# 8__MOT_CONNECTOR.net
KiCad netlist of a schematic drawn in Altium Designer
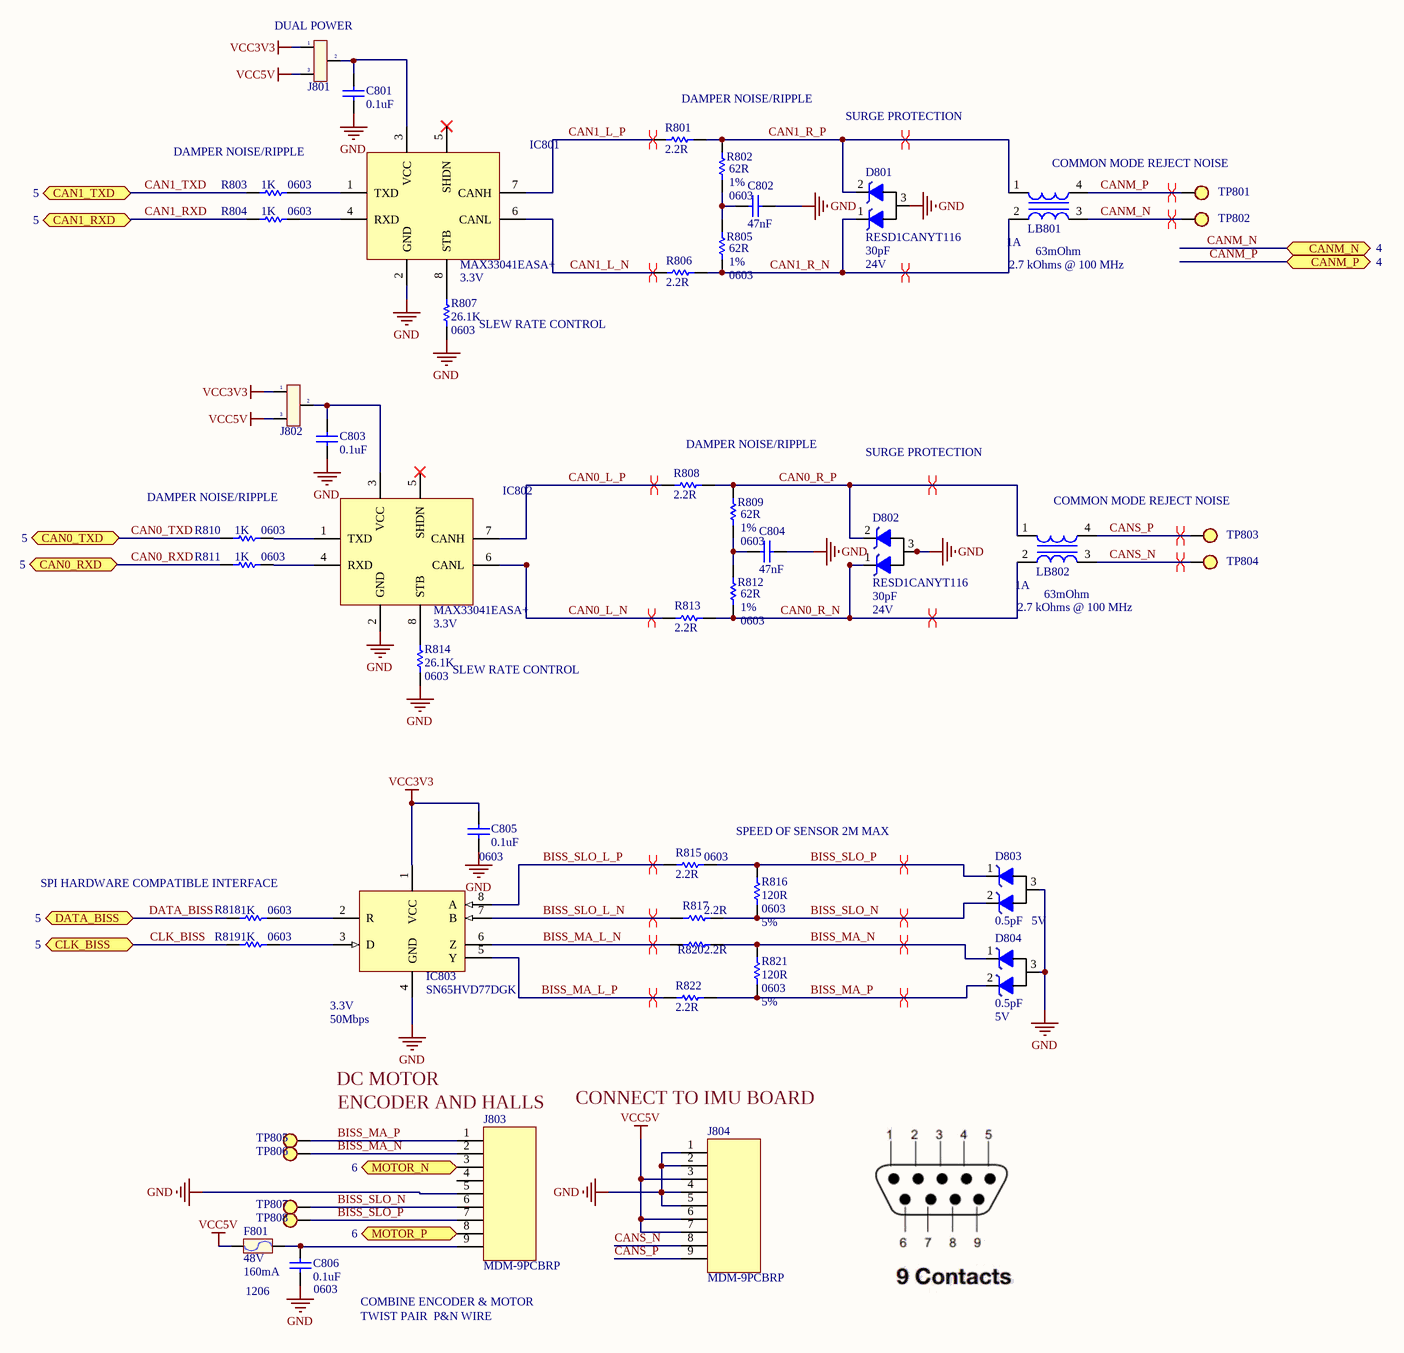
[diagram p0: [8]_MOT_CONNECTOR.SchDoc]

(export (version "E")
  (design (tool "Eeschema 10.0.6"))
  (components
    (comp (ref "C801")
      (value "0.1uF")
      (footprint "CAP 0603")
      (description "CAP-CER,SMD;0.1UF,10%,50V,X7R,0603")
      (fields (field (name "VOLTAGE") "50V") (field (name "TOLERANCE") "±10%"))
      (libsource (lib "Slider") (part "Cap"))
    )
    (comp (ref "C802")
      (value "47nF")
      (footprint "CAP 0603")
      (description "CAP-CER,SMD; 47nF,10%,50V,X7R,0603")
      (fields (field (name "VOLTAGE") "50V") (field (name "TOLERANCE") "±10%"))
      (libsource (lib "Slider") (part "Cap"))
    )
    (comp (ref "C803")
      (value "0.1uF")
      (footprint "CAP 0603")
      (description "CAP-CER,SMD;0.1UF,10%,50V,X7R,0603")
      (fields (field (name "VOLTAGE") "50V") (field (name "TOLERANCE") "±10%"))
      (libsource (lib "Slider") (part "Cap"))
    )
    (comp (ref "C804")
      (value "47nF")
      (footprint "CAP 0603")
      (description "CAP-CER,SMD; 47nF,10%,50V,X7R,0603")
      (fields (field (name "VOLTAGE") "50V") (field (name "TOLERANCE") "±10%"))
      (libsource (lib "Slider") (part "Cap"))
    )
    (comp (ref "C805")
      (value "0.1uF")
      (footprint "0603")
      (description "CAP-CER,SMD;0.1UF,10%,50V,X7R,0603")
      (fields (field (name "VOLTAGE") "50V") (field (name "TOLERANCE") "±10%"))
      (libsource (lib "Slider") (part "Cap"))
    )
    (comp (ref "C806")
      (value "0.1uF")
      (footprint "0603")
      (description "CAP-CER,SMD;0.1UF,10%,50V,X7R,0603")
      (fields (field (name "VOLTAGE") "50V") (field (name "TOLERANCE") "±10%"))
      (libsource (lib "Slider") (part "Cap"))
    )
    (comp (ref "D801")
      (value "RESD1CANYT116")
      (footprint "SOT-23-3")
      (description "TVS DIODE 24VWM 50VC SOT23-")
      (fields
        (field (name "POWER") "230W")
        (field (name "CAPACITANCE") "30pF")
        (field (name "VOLTAGE") "24V")
      )
      (libsource (lib "My Library") (part "TVS_DUAL_SIGNAL_5V_SOT23"))
    )
    (comp (ref "D802")
      (value "RESD1CANYT116")
      (footprint "SOT-23-3")
      (description "TVS DIODE 24VWM 50VC SOT23-")
      (fields
        (field (name "POWER") "230W")
        (field (name "CAPACITANCE") "30pF")
        (field (name "VOLTAGE") "24V")
      )
      (libsource (lib "My Library") (part "TVS_DUAL_SIGNAL_5V_SOT23"))
    )
    (comp (ref "D803")
      (value "ESDR0502BT1G")
      (footprint "SOT-416")
      (description "5V, ESD PROTECTION DEVICES, SOT-23")
      (fields
        (field (name "MANUFACTURER2_PART#") "DF3D6.8MS,LF")
        (field (name "POWER") "320W")
        (field (name "CAPACITANCE") "0.5pF")
        (field (name "VOLTAGE") "5V")
      )
      (libsource (lib "") (part "TVS_DUAL_SIGNAL_5V_SOT23_1"))
    )
    (comp (ref "D804")
      (value "ESDR0502BT1G")
      (footprint "SOT-416")
      (description "5V, ESD PROTECTION DEVICES, SOT-23")
      (fields
        (field (name "MANUFACTURER2_PART#") "DF3D6.8MS,LF")
        (field (name "POWER") "320W")
        (field (name "CAPACITANCE") "0.5pF")
        (field (name "VOLTAGE") "5V")
      )
      (libsource (lib "") (part "TVS_DUAL_SIGNAL_5V_SOT23_1"))
    )
    (comp (ref "F801")
      (value "0ZCG0014FF2C")
      (footprint "RES 1206")
      (description "PTC RESET FUSE 48V 160MA 1206")
      (fields
        (field (name "MANUFACTURER1_PART#") "0ZCJ0016FF2E")
        (field (name "MANUFACTURER2_PART#") "CLA1684")
        (field (name "VOLTAGE - RATED") "48V")
        (field (name "PACKAGE / CASE") "1206")
        (field (name "CURRENT RATING (AMPS)") "160mA")
      )
      (libsource (lib "K Shematic") (part "0875.800MXEP"))
    )
    (comp (ref "IC801")
      (value "MAX33041EASA+")
      (footprint "8-SOIC")
      (description "IC CAN TXRX 3.3V 2MBPS SOIC")
      (fields (field (name "MANUFACTURER PART NUMBER") "MAX33041EASA+") (field (name "VOLTAGE") "3.3V"))
      (libsource (lib "OE Seeker-IsolatedPower") (part "IC;IC CAN TRANSEIVER HS,8SOIC,-40TO150°C,TJA1042T/3,118"))
    )
    (comp (ref "IC802")
      (value "MAX33041EASA+")
      (footprint "8-SOIC")
      (description "IC CAN TXRX 3.3V 2MBPS SOIC")
      (fields (field (name "MANUFACTURER PART NUMBER") "MAX33041EASA+") (field (name "VOLTAGE") "3.3V"))
      (libsource (lib "OE Seeker-IsolatedPower") (part "IC;IC CAN TRANSEIVER HS,8SOIC,-40TO150°C,TJA1042T/3,118"))
    )
    (comp (ref "IC803")
      (value "IC;IC TRANSCEIVER FULL 1/1 8SOIC,8-SOIC,-40TO 85°C,SN65HVD77DR")
      (footprint "8-VSSOP")
      (description "IC TRANSCEIVER FULL 1/1 8VSSOP")
      (fields
        (field (name "MANUFACTURER") "TI")
        (field (name "MANUFACTURER PART NUMBER") "SN65HVD77DGK")
        (field (name "MANUFACTURER1_PART#") "SN65HVD77DGK")
        (field (name "VOLTAGE") "3.3V")
        (field (name "SPEED") "50Mbps")
      )
      (libsource (lib "DRIVER MOTION TILT_NEW") (part "IC;IC TRANSCEIVER FULL 1/1 8SOIC,8-SOIC,-40TO 85°C,SN65HVD77DR"))
    )
    (comp (ref "J801")
      (value "JP 2-1")
      (footprint "JP3")
      (description "Jumper 2-1")
      (libsource (lib "ThanhSchematicLib") (part "JP 2-1"))
    )
    (comp (ref "J802")
      (value "JP 2-1")
      (footprint "JP3")
      (description "Jumper 2-1")
      (libsource (lib "ThanhSchematicLib") (part "JP 2-1"))
    )
    (comp (ref "J803")
      (value "CONN-DIP;CONN MICRO-D PLUG 9POS R/A SLDR,M,MDM-9PCBRP")
      (footprint "MDM-9PCBRP")
      (description "CONN MICRO-D PLUG 9POS R/A SLDR")
      (fields
        (field (name "MANUFACTURER") "ITT CANNON, LLC")
        (field (name "MANUFACTURER PART NUMBER") "MDM-9PCBRP")
        (field (name "MANUFACTURER1_PART#") "MDM-9PCBRP")
      )
      (libsource (lib "DRIVER MOTION PAN_NEW") (part "CONN-DIP;CONN MICRO-D PLUG 9POS R/A SLDR,M,MDM-9PCBRP"))
    )
    (comp (ref "J804")
      (value "CONN-DIP;CONN MICRO-D PLUG 9POS R/A SLDR,M,MDM-9PCBRP")
      (footprint "MDM-9PCBRP")
      (description "CONN MICRO-D PLUG 9POS R/A SLDR")
      (fields
        (field (name "MANUFACTURER") "ITT CANNON, LLC")
        (field (name "MANUFACTURER PART NUMBER") "MDM-9PCBRP")
        (field (name "MANUFACTURER1_PART#") "MDM-9PCBRP")
      )
      (libsource (lib "IMU_NEW") (part "CONN-DIP;CONN MICRO-D PLUG 9POS R/A SLDR,M,MDM-9PCBRP"))
    )
    (comp (ref "LB801")
      (value "MCM-7060M-272-RU")
      (footprint "MCM-7060M")
      (description "CMC 1A 2LN 2.7KOHM SMD")
      (fields
        (field (name "CURRENT") "1A")
        (field (name "IMPEDANCE") "2.7 kOhms @ 100 MHz")
        (field (name "DCR") "63mOhm")
      )
      (libsource (lib "OE Seeker-IsolatedPower") (part "CHOKE-SMD;90OHM@100MHz,0.15A,5V,DLP11SA900HL2L"))
    )
    (comp (ref "LB802")
      (value "MCM-7060M-272-RU")
      (footprint "MCM-7060M")
      (description "CMC 1A 2LN 2.7KOHM SMD")
      (fields
        (field (name "CURRENT") "1A")
        (field (name "IMPEDANCE") "2.7 kOhms @ 100 MHz")
        (field (name "DCR") "63mOhm")
      )
      (libsource (lib "OE Seeker-IsolatedPower") (part "CHOKE-SMD;90OHM@100MHz,0.15A,5V,DLP11SA900HL2L"))
    )
    (comp (ref "R801")
      (value "2.2R")
      (footprint "res 0603")
      (description "RES SMD 2.2 OHM 5% 1/10W 0603")
      (fields
        (field (name "MANUFACTURER1_PART#") "RC0603JR-072R2L")
        (field (name "MANUFACTURER2_PART#") "RMCF0603JT2R20")
      )
      (libsource (lib "Full") (part "Res0.3"))
    )
    (comp (ref "R802")
      (value "62R")
      (footprint "R0603")
      (description "RES SM 62 OHM 1% 1/10W 0603")
      (fields
        (field (name "MANUFACTURER1_PART#") "RMCF0603FT62R0")
        (field (name "MANUFACTURER2_PART#") "RC0603FR-0762RL")
        (field (name "TOLERANCE") "1%")
        (field (name "PACKAGE") "0603")
      )
      (libsource (lib "OE Seeker-IsolatedPower") (part "RES-SMD;60.4OHM,1%,0402,1/10W"))
    )
    (comp (ref "R803")
      (value "1K")
      (footprint "res 0603")
      (description "RES SMD,1K OHM,5%,1/10W,0603")
      (fields
        (field (name "MANUFACTURER1_PART#") "RMCF06031K00JNEAC")
        (field (name "MANUFACTURER2_PART#") "R0603J1KTG")
        (field (name "PCB FOOTPRINT") "0603")
      )
      (libsource (lib "Full") (part "Res0.3"))
    )
    (comp (ref "R804")
      (value "1K")
      (footprint "res 0603")
      (description "RES SMD,1K OHM,5%,1/10W,0603")
      (fields
        (field (name "MANUFACTURER1_PART#") "RMCF06031K00JNEAC")
        (field (name "MANUFACTURER2_PART#") "R0603J1KTG")
        (field (name "PCB FOOTPRINT") "0603")
      )
      (libsource (lib "Full") (part "Res0.3"))
    )
    (comp (ref "R805")
      (value "62R")
      (footprint "R0603")
      (description "RES SM 62 OHM 1% 1/10W 0603")
      (fields
        (field (name "MANUFACTURER1_PART#") "RMCF0603FT62R0")
        (field (name "MANUFACTURER2_PART#") "RC0603FR-0762RL")
        (field (name "TOLERANCE") "1%")
        (field (name "PACKAGE") "0603")
      )
      (libsource (lib "OE Seeker-IsolatedPower") (part "RES-SMD;60.4OHM,1%,0402,1/10W"))
    )
    (comp (ref "R806")
      (value "2.2R")
      (footprint "res 0603")
      (description "RES SMD 2.2 OHM 5% 1/10W 0603")
      (fields
        (field (name "MANUFACTURER1_PART#") "RC0603JR-072R2L")
        (field (name "MANUFACTURER2_PART#") "RMCF0603JT2R20")
      )
      (libsource (lib "Full") (part "Res0.3"))
    )
    (comp (ref "R807")
      (value "26.1K")
      (footprint "R0603")
      (description "RES 26.1K OHM 1% 1/10W 0603")
      (fields
        (field (name "MANUFACTURER1_PART#") "RMCF0603FT26K1")
        (field (name "MANUFACTURER2_PART#") "RC0603FR-0726K1L")
        (field (name "PCB FOOTPRINT") "0603")
      )
      (libsource (lib "altium-import") (part "root_3_Res0.3_"))
    )
    (comp (ref "R808")
      (value "2.2R")
      (footprint "res 0603")
      (description "RES SMD 2.2 OHM 5% 1/10W 0603")
      (fields
        (field (name "MANUFACTURER1_PART#") "RC0603JR-072R2L")
        (field (name "MANUFACTURER2_PART#") "RMCF0603JT2R20")
      )
      (libsource (lib "Full") (part "Res0.3"))
    )
    (comp (ref "R809")
      (value "62R")
      (footprint "R0603")
      (description "RES SM 62 OHM 1% 1/10W 0603")
      (fields
        (field (name "MANUFACTURER1_PART#") "RMCF0603FT62R0")
        (field (name "MANUFACTURER2_PART#") "RC0603FR-0762RL")
        (field (name "TOLERANCE") "1%")
        (field (name "PACKAGE") "0603")
      )
      (libsource (lib "OE Seeker-IsolatedPower") (part "RES-SMD;60.4OHM,1%,0402,1/10W"))
    )
    (comp (ref "R810")
      (value "1K")
      (footprint "res 0603")
      (description "RES SMD,1K OHM,5%,1/10W,0603")
      (fields
        (field (name "MANUFACTURER1_PART#") "RMCF06031K00JNEAC")
        (field (name "MANUFACTURER2_PART#") "R0603J1KTG")
        (field (name "PCB FOOTPRINT") "0603")
      )
      (libsource (lib "Full") (part "Res0.3"))
    )
    (comp (ref "R811")
      (value "1K")
      (footprint "res 0603")
      (description "RES SMD,1K OHM,5%,1/10W,0603")
      (fields
        (field (name "MANUFACTURER1_PART#") "RMCF06031K00JNEAC")
        (field (name "MANUFACTURER2_PART#") "R0603J1KTG")
        (field (name "PCB FOOTPRINT") "0603")
      )
      (libsource (lib "Full") (part "Res0.3"))
    )
    (comp (ref "R812")
      (value "62R")
      (footprint "R0603")
      (description "RES SM 62 OHM 1% 1/10W 0603")
      (fields
        (field (name "MANUFACTURER1_PART#") "RMCF0603FT62R0")
        (field (name "MANUFACTURER2_PART#") "RC0603FR-0762RL")
        (field (name "TOLERANCE") "1%")
        (field (name "PACKAGE") "0603")
      )
      (libsource (lib "OE Seeker-IsolatedPower") (part "RES-SMD;60.4OHM,1%,0402,1/10W"))
    )
    (comp (ref "R813")
      (value "2.2R")
      (footprint "res 0603")
      (description "RES SMD 2.2 OHM 5% 1/10W 0603")
      (fields
        (field (name "MANUFACTURER1_PART#") "RC0603JR-072R2L")
        (field (name "MANUFACTURER2_PART#") "RMCF0603JT2R20")
      )
      (libsource (lib "Full") (part "Res0.3"))
    )
    (comp (ref "R814")
      (value "26.1K")
      (footprint "R0603")
      (description "RES 26.1K OHM 1% 1/10W 0603")
      (fields
        (field (name "MANUFACTURER1_PART#") "RMCF0603FT26K1")
        (field (name "MANUFACTURER2_PART#") "RC0603FR-0726K1L")
        (field (name "PCB FOOTPRINT") "0603")
      )
      (libsource (lib "altium-import") (part "root_3_Res0.3_"))
    )
    (comp (ref "R815")
      (value "2.2R")
      (footprint "res 0603")
      (description "RES SMD 2.2 OHM 5% 1/10W 0603")
      (fields
        (field (name "MANUFACTURER1_PART#") "RC0603JR-072R2L")
        (field (name "MANUFACTURER2_PART#") "RMCF0603JT2R20")
        (field (name "PCB FOOTPRINT") "0603")
      )
      (libsource (lib "Full") (part "Res0.3"))
    )
    (comp (ref "R816")
      (value "120R")
      (footprint "res 0603")
      (description "RES 120 OHM 5% 1/10W 0603")
      (fields
        (field (name "MANUFACTURER1_PART#") "RMCF0603JG120R")
        (field (name "PCB_ FOOTPRINT") "0603")
        (field (name "TOLERANCE") "5%")
      )
      (libsource (lib "thuvien") (part "RES 120 OHM 5% 1/10W 0603"))
    )
    (comp (ref "R817")
      (value "2.2R")
      (footprint "res 0603")
      (description "RES SMD 2.2 OHM 5% 1/10W 0603")
      (fields
        (field (name "MANUFACTURER1_PART#") "RC0603JR-072R2L")
        (field (name "MANUFACTURER2_PART#") "RMCF0603JT2R20")
      )
      (libsource (lib "Full") (part "Res0.3"))
    )
    (comp (ref "R818")
      (value "1K")
      (footprint "res 0603")
      (description "RES SMD,1K OHM,5%,1/10W,0603")
      (fields
        (field (name "MANUFACTURER1_PART#") "RMCF06031K00JNEAC")
        (field (name "MANUFACTURER2_PART#") "R0603J1KTG")
        (field (name "PCB FOOTPRINT") "0603")
      )
      (libsource (lib "Full") (part "Res0.3"))
    )
    (comp (ref "R819")
      (value "1K")
      (footprint "res 0603")
      (description "RES SMD,1K OHM,5%,1/10W,0603")
      (fields
        (field (name "MANUFACTURER1_PART#") "RMCF06031K00JNEAC")
        (field (name "MANUFACTURER2_PART#") "R0603J1KTG")
        (field (name "PCB FOOTPRINT") "0603")
      )
      (libsource (lib "Full") (part "Res0.3"))
    )
    (comp (ref "R820")
      (value "2.2R")
      (footprint "res 0603")
      (description "RES SMD 2.2 OHM 5% 1/10W 0603")
      (fields
        (field (name "MANUFACTURER1_PART#") "RC0603JR-072R2L")
        (field (name "MANUFACTURER2_PART#") "RMCF0603JT2R20")
      )
      (libsource (lib "Full") (part "Res0.3"))
    )
    (comp (ref "R821")
      (value "120R")
      (footprint "res 0603")
      (description "RES 120 OHM 5% 1/10W 0603")
      (fields
        (field (name "MANUFACTURER1_PART#") "RMCF0603JG120R")
        (field (name "PCB_ FOOTPRINT") "0603")
        (field (name "TOLERANCE") "5%")
      )
      (libsource (lib "thuvien") (part "RES 120 OHM 5% 1/10W 0603"))
    )
    (comp (ref "R822")
      (value "2.2R")
      (footprint "res 0603")
      (description "RES SMD 2.2 OHM 5% 1/10W 0603")
      (fields
        (field (name "MANUFACTURER1_PART#") "RC0603JR-072R2L")
        (field (name "MANUFACTURER2_PART#") "RMCF0603JT2R20")
      )
      (libsource (lib "Full") (part "Res0.3"))
    )
    (comp (ref "TP801")
      (value "TP SMD")
      (footprint "TESTPOINT")
      (description "TEST POINT")
      (libsource (lib "VSM") (part "TP SMD"))
    )
    (comp (ref "TP802")
      (value "TP SMD")
      (footprint "TESTPOINT")
      (description "TEST POINT")
      (libsource (lib "VSM") (part "TP SMD"))
    )
    (comp (ref "TP803")
      (value "TP SMD")
      (footprint "TESTPOINT")
      (description "TEST POINT")
      (libsource (lib "VSM") (part "TP SMD"))
    )
    (comp (ref "TP804")
      (value "TP SMD")
      (footprint "TESTPOINT")
      (description "TEST POINT")
      (libsource (lib "VSM") (part "TP SMD"))
    )
    (comp (ref "TP805")
      (value "TP SMD")
      (footprint "TESTPOINT")
      (description "TEST POINT")
      (libsource (lib "VSM") (part "TP SMD"))
    )
    (comp (ref "TP806")
      (value "TP SMD")
      (footprint "TESTPOINT")
      (description "TEST POINT")
      (libsource (lib "VSM") (part "TP SMD"))
    )
    (comp (ref "TP807")
      (value "TP SMD")
      (footprint "TESTPOINT")
      (description "TEST POINT")
      (libsource (lib "VSM") (part "TP SMD"))
    )
    (comp (ref "TP808")
      (value "TP SMD")
      (footprint "TESTPOINT")
      (description "TEST POINT")
      (libsource (lib "VSM") (part "TP SMD"))
    )
  )
  (nets
    (net (code "1") (name "/BISS_MA_L_N") (class "Default")
      (node (ref "IC803") (pin "6") (pinfunction "Z_6") (pintype "passive"))
      (node (ref "R820") (pin "2") (pinfunction "2_2") (pintype "passive"))
    )
    (net (code "2") (name "/BISS_MA_L_P") (class "Default")
      (node (ref "IC803") (pin "5") (pinfunction "Y_5") (pintype "passive"))
      (node (ref "R822") (pin "2") (pinfunction "2_2") (pintype "passive"))
    )
    (net (code "3") (name "/BISS_MA_N") (class "Default")
      (node (ref "D804") (pin "1") (pinfunction "K_1") (pintype "passive"))
      (node (ref "J803") (pin "2") (pinfunction "2_2") (pintype "passive"))
      (node (ref "R820") (pin "1") (pinfunction "1_1") (pintype "passive"))
      (node (ref "R821") (pin "1") (pinfunction "1_1") (pintype "passive"))
      (node (ref "TP806") (pin "1") (pinfunction "1_1") (pintype "passive"))
    )
    (net (code "4") (name "/BISS_MA_P") (class "Default")
      (node (ref "D804") (pin "2") (pinfunction "K_2") (pintype "passive"))
      (node (ref "J803") (pin "1") (pinfunction "1_1") (pintype "passive"))
      (node (ref "R821") (pin "2") (pinfunction "2_2") (pintype "passive"))
      (node (ref "R822") (pin "1") (pinfunction "1_1") (pintype "passive"))
      (node (ref "TP805") (pin "1") (pinfunction "1_1") (pintype "passive"))
    )
    (net (code "5") (name "/BISS_SLO_L_N") (class "Default")
      (node (ref "IC803") (pin "7") (pinfunction "B_7") (pintype "input"))
      (node (ref "R817") (pin "2") (pinfunction "2_2") (pintype "passive"))
    )
    (net (code "6") (name "/BISS_SLO_L_P") (class "Default")
      (node (ref "IC803") (pin "8") (pinfunction "A_8") (pintype "input"))
      (node (ref "R815") (pin "2") (pinfunction "2_2") (pintype "passive"))
    )
    (net (code "7") (name "/BISS_SLO_N") (class "Default")
      (node (ref "D803") (pin "2") (pinfunction "K_2") (pintype "passive"))
      (node (ref "J803") (pin "6") (pinfunction "6_6") (pintype "passive"))
      (node (ref "R816") (pin "2") (pinfunction "2_2") (pintype "passive"))
      (node (ref "R817") (pin "1") (pinfunction "1_1") (pintype "passive"))
      (node (ref "TP807") (pin "1") (pinfunction "1_1") (pintype "passive"))
    )
    (net (code "8") (name "/BISS_SLO_P") (class "Default")
      (node (ref "D803") (pin "1") (pinfunction "K_1") (pintype "passive"))
      (node (ref "J803") (pin "7") (pinfunction "7_7") (pintype "passive"))
      (node (ref "R815") (pin "1") (pinfunction "1_1") (pintype "passive"))
      (node (ref "R816") (pin "1") (pinfunction "1_1") (pintype "passive"))
      (node (ref "TP808") (pin "1") (pinfunction "1_1") (pintype "passive"))
    )
    (net (code "9") (name "/CAN0_L_N") (class "Default")
      (node (ref "IC802") (pin "6") (pinfunction "CANL_6") (pintype "passive"))
      (node (ref "R813") (pin "2") (pinfunction "2_2") (pintype "passive"))
    )
    (net (code "10") (name "/CAN0_L_P") (class "Default")
      (node (ref "IC802") (pin "7") (pinfunction "CANH_7") (pintype "passive"))
      (node (ref "R808") (pin "2") (pinfunction "2_2") (pintype "passive"))
    )
    (net (code "11") (name "/CAN0_RXD") (class "Default")
      (node (ref "R811") (pin "2") (pinfunction "2_2") (pintype "passive"))
    )
    (net (code "12") (name "/CAN0_R_N") (class "Default")
      (node (ref "D802") (pin "1") (pinfunction "K_1") (pintype "passive"))
      (node (ref "LB802") (pin "2") (pinfunction "2_2") (pintype "passive"))
      (node (ref "R812") (pin "1") (pinfunction "1_1") (pintype "passive"))
      (node (ref "R813") (pin "1") (pinfunction "1_1") (pintype "passive"))
    )
    (net (code "13") (name "/CAN0_R_P") (class "Default")
      (node (ref "D802") (pin "2") (pinfunction "K_2") (pintype "passive"))
      (node (ref "LB802") (pin "1") (pinfunction "1_1") (pintype "passive"))
      (node (ref "R808") (pin "1") (pinfunction "1_1") (pintype "passive"))
      (node (ref "R809") (pin "2") (pinfunction "2_2") (pintype "passive"))
    )
    (net (code "14") (name "/CAN0_TXD") (class "Default")
      (node (ref "R810") (pin "2") (pinfunction "2_2") (pintype "passive"))
    )
    (net (code "15") (name "/CAN1_L_N") (class "Default")
      (node (ref "IC801") (pin "6") (pinfunction "CANL_6") (pintype "passive"))
      (node (ref "R806") (pin "2") (pinfunction "2_2") (pintype "passive"))
    )
    (net (code "16") (name "/CAN1_L_P") (class "Default")
      (node (ref "IC801") (pin "7") (pinfunction "CANH_7") (pintype "passive"))
      (node (ref "R801") (pin "2") (pinfunction "2_2") (pintype "passive"))
    )
    (net (code "17") (name "/CAN1_RXD") (class "Default")
      (node (ref "R804") (pin "2") (pinfunction "2_2") (pintype "passive"))
    )
    (net (code "18") (name "/CAN1_R_N") (class "Default")
      (node (ref "D801") (pin "1") (pinfunction "K_1") (pintype "passive"))
      (node (ref "LB801") (pin "2") (pinfunction "2_2") (pintype "passive"))
      (node (ref "R805") (pin "1") (pinfunction "1_1") (pintype "passive"))
      (node (ref "R806") (pin "1") (pinfunction "1_1") (pintype "passive"))
    )
    (net (code "19") (name "/CAN1_R_P") (class "Default")
      (node (ref "D801") (pin "2") (pinfunction "K_2") (pintype "passive"))
      (node (ref "LB801") (pin "1") (pinfunction "1_1") (pintype "passive"))
      (node (ref "R801") (pin "1") (pinfunction "1_1") (pintype "passive"))
      (node (ref "R802") (pin "2") (pinfunction "2_2") (pintype "passive"))
    )
    (net (code "20") (name "/CAN1_TXD") (class "Default")
      (node (ref "R803") (pin "2") (pinfunction "2_2") (pintype "passive"))
    )
    (net (code "21") (name "/CANM_N") (class "Default")
      (node (ref "LB801") (pin "3") (pinfunction "3_3") (pintype "passive"))
      (node (ref "TP802") (pin "1") (pinfunction "1_1") (pintype "passive"))
    )
    (net (code "22") (name "/CANM_P") (class "Default")
      (node (ref "LB801") (pin "4") (pinfunction "4_4") (pintype "passive"))
      (node (ref "TP801") (pin "1") (pinfunction "1_1") (pintype "passive"))
    )
    (net (code "23") (name "/CANS_N") (class "Default")
      (node (ref "J804") (pin "8") (pinfunction "8_8") (pintype "passive"))
      (node (ref "LB802") (pin "3") (pinfunction "3_3") (pintype "passive"))
      (node (ref "TP804") (pin "1") (pinfunction "1_1") (pintype "passive"))
    )
    (net (code "24") (name "/CANS_P") (class "Default")
      (node (ref "J804") (pin "9") (pinfunction "9_9") (pintype "passive"))
      (node (ref "LB802") (pin "4") (pinfunction "4_4") (pintype "passive"))
      (node (ref "TP803") (pin "1") (pinfunction "1_1") (pintype "passive"))
    )
    (net (code "25") (name "/CLK_BISS") (class "Default")
      (node (ref "R819") (pin "2") (pinfunction "2_2") (pintype "passive"))
    )
    (net (code "26") (name "/DATA_BISS") (class "Default")
      (node (ref "R818") (pin "2") (pinfunction "2_2") (pintype "passive"))
    )
    (net (code "27") (name "/MOTOR_N") (class "Default")
      (node (ref "J803") (pin "3") (pinfunction "3_3") (pintype "passive"))
    )
    (net (code "28") (name "/MOTOR_P") (class "Default")
      (node (ref "J803") (pin "8") (pinfunction "8_8") (pintype "passive"))
    )
    (net (code "29") (name "GND") (class "Default")
      (node (ref "C801") (pin "2") (pinfunction "2_2") (pintype "passive"))
      (node (ref "C802") (pin "2") (pinfunction "2_2") (pintype "passive"))
      (node (ref "C803") (pin "2") (pinfunction "2_2") (pintype "passive"))
      (node (ref "C804") (pin "2") (pinfunction "2_2") (pintype "passive"))
      (node (ref "C805") (pin "2") (pinfunction "2_2") (pintype "passive"))
      (node (ref "C806") (pin "2") (pinfunction "2_2") (pintype "passive"))
      (node (ref "D801") (pin "3") (pinfunction "A_3") (pintype "passive"))
      (node (ref "D802") (pin "3") (pinfunction "A_3") (pintype "passive"))
      (node (ref "D803") (pin "3") (pinfunction "A_3") (pintype "passive"))
      (node (ref "D804") (pin "3") (pinfunction "A_3") (pintype "passive"))
      (node (ref "IC801") (pin "2") (pinfunction "GND_2") (pintype "passive"))
      (node (ref "IC802") (pin "2") (pinfunction "GND_2") (pintype "passive"))
      (node (ref "IC803") (pin "4") (pinfunction "GND_4") (pintype "passive"))
      (node (ref "J803") (pin "5") (pinfunction "5_5") (pintype "passive"))
      (node (ref "J804") (pin "1") (pinfunction "1_1") (pintype "passive"))
      (node (ref "J804") (pin "2") (pinfunction "2_2") (pintype "passive"))
      (node (ref "J804") (pin "4") (pinfunction "4_4") (pintype "passive"))
      (node (ref "J804") (pin "5") (pinfunction "5_5") (pintype "passive"))
      (node (ref "R807") (pin "2") (pinfunction "2_2") (pintype "passive"))
      (node (ref "R814") (pin "2") (pinfunction "2_2") (pintype "passive"))
    )
    (net (code "30") (name "Net-(C802-Pad1)") (class "Default")
      (node (ref "C802") (pin "1") (pinfunction "1_1") (pintype "passive"))
      (node (ref "R802") (pin "1") (pinfunction "1_1") (pintype "passive"))
      (node (ref "R805") (pin "2") (pinfunction "2_2") (pintype "passive"))
    )
    (net (code "31") (name "Net-(C804-Pad1)") (class "Default")
      (node (ref "C804") (pin "1") (pinfunction "1_1") (pintype "passive"))
      (node (ref "R809") (pin "1") (pinfunction "1_1") (pintype "passive"))
      (node (ref "R812") (pin "2") (pinfunction "2_2") (pintype "passive"))
    )
    (net (code "32") (name "Net-(C806-Pad1)") (class "Default")
      (node (ref "C806") (pin "1") (pinfunction "1_1") (pintype "passive"))
      (node (ref "F801") (pin "1") (pinfunction "1_1") (pintype "passive"))
      (node (ref "J803") (pin "9") (pinfunction "9_9") (pintype "passive"))
    )
    (net (code "33") (name "Net-(IC801-RXD)") (class "Default")
      (node (ref "IC801") (pin "4") (pinfunction "RXD_4") (pintype "passive"))
      (node (ref "R804") (pin "1") (pinfunction "1_1") (pintype "passive"))
    )
    (net (code "34") (name "Net-(IC801-STB)") (class "Default")
      (node (ref "IC801") (pin "8") (pinfunction "STB_8") (pintype "passive"))
      (node (ref "R807") (pin "1") (pinfunction "1_1") (pintype "passive"))
    )
    (net (code "35") (name "Net-(IC801-TXD)") (class "Default")
      (node (ref "IC801") (pin "1") (pinfunction "TXD_1") (pintype "passive"))
      (node (ref "R803") (pin "1") (pinfunction "1_1") (pintype "passive"))
    )
    (net (code "36") (name "Net-(IC801-VCC)") (class "Default")
      (node (ref "C801") (pin "1") (pinfunction "1_1") (pintype "passive"))
      (node (ref "IC801") (pin "3") (pinfunction "VCC_3") (pintype "passive"))
      (node (ref "J801") (pin "2") (pinfunction "2_2") (pintype "passive"))
    )
    (net (code "37") (name "Net-(IC802-RXD)") (class "Default")
      (node (ref "IC802") (pin "4") (pinfunction "RXD_4") (pintype "passive"))
      (node (ref "R811") (pin "1") (pinfunction "1_1") (pintype "passive"))
    )
    (net (code "38") (name "Net-(IC802-STB)") (class "Default")
      (node (ref "IC802") (pin "8") (pinfunction "STB_8") (pintype "passive"))
      (node (ref "R814") (pin "1") (pinfunction "1_1") (pintype "passive"))
    )
    (net (code "39") (name "Net-(IC802-TXD)") (class "Default")
      (node (ref "IC802") (pin "1") (pinfunction "TXD_1") (pintype "passive"))
      (node (ref "R810") (pin "1") (pinfunction "1_1") (pintype "passive"))
    )
    (net (code "40") (name "Net-(IC802-VCC)") (class "Default")
      (node (ref "C803") (pin "1") (pinfunction "1_1") (pintype "passive"))
      (node (ref "IC802") (pin "3") (pinfunction "VCC_3") (pintype "passive"))
      (node (ref "J802") (pin "2") (pinfunction "2_2") (pintype "passive"))
    )
    (net (code "41") (name "Net-(IC803-D)") (class "Default")
      (node (ref "IC803") (pin "3") (pinfunction "D_3") (pintype "input"))
      (node (ref "R819") (pin "1") (pinfunction "1_1") (pintype "passive"))
    )
    (net (code "42") (name "Net-(IC803-R)") (class "Default")
      (node (ref "IC803") (pin "2") (pinfunction "R_2") (pintype "passive"))
      (node (ref "R818") (pin "1") (pinfunction "1_1") (pintype "passive"))
    )
    (net (code "43") (name "VCC3V3") (class "Default")
      (node (ref "C805") (pin "1") (pinfunction "1_1") (pintype "passive"))
      (node (ref "IC803") (pin "1") (pinfunction "VCC_1") (pintype "passive"))
      (node (ref "J801") (pin "1") (pinfunction "1_1") (pintype "passive"))
      (node (ref "J802") (pin "1") (pinfunction "1_1") (pintype "passive"))
    )
    (net (code "44") (name "VCC5V") (class "Default")
      (node (ref "F801") (pin "2") (pinfunction "2_2") (pintype "passive"))
      (node (ref "J801") (pin "3") (pinfunction "3_3") (pintype "passive"))
      (node (ref "J802") (pin "3") (pinfunction "3_3") (pintype "passive"))
      (node (ref "J804") (pin "3") (pinfunction "3_3") (pintype "passive"))
      (node (ref "J804") (pin "6") (pinfunction "6_6") (pintype "passive"))
      (node (ref "J804") (pin "7") (pinfunction "7_7") (pintype "passive"))
    )
    (net (code "45") (name "unconnected-(IC801-SHDN-Pad5)") (class "Default")
      (node (ref "IC801") (pin "5") (pinfunction "SHDN_5") (pintype "passive+no_connect"))
    )
    (net (code "46") (name "unconnected-(IC802-SHDN-Pad5)") (class "Default")
      (node (ref "IC802") (pin "5") (pinfunction "SHDN_5") (pintype "passive+no_connect"))
    )
    (net (code "47") (name "unconnected-(J803-Pad4)") (class "Default")
      (node (ref "J803") (pin "4") (pinfunction "4_4") (pintype "passive"))
    )
  )
)
